# NixieDriver.net
KiCad netlist of a schematic drawn in EAGLE
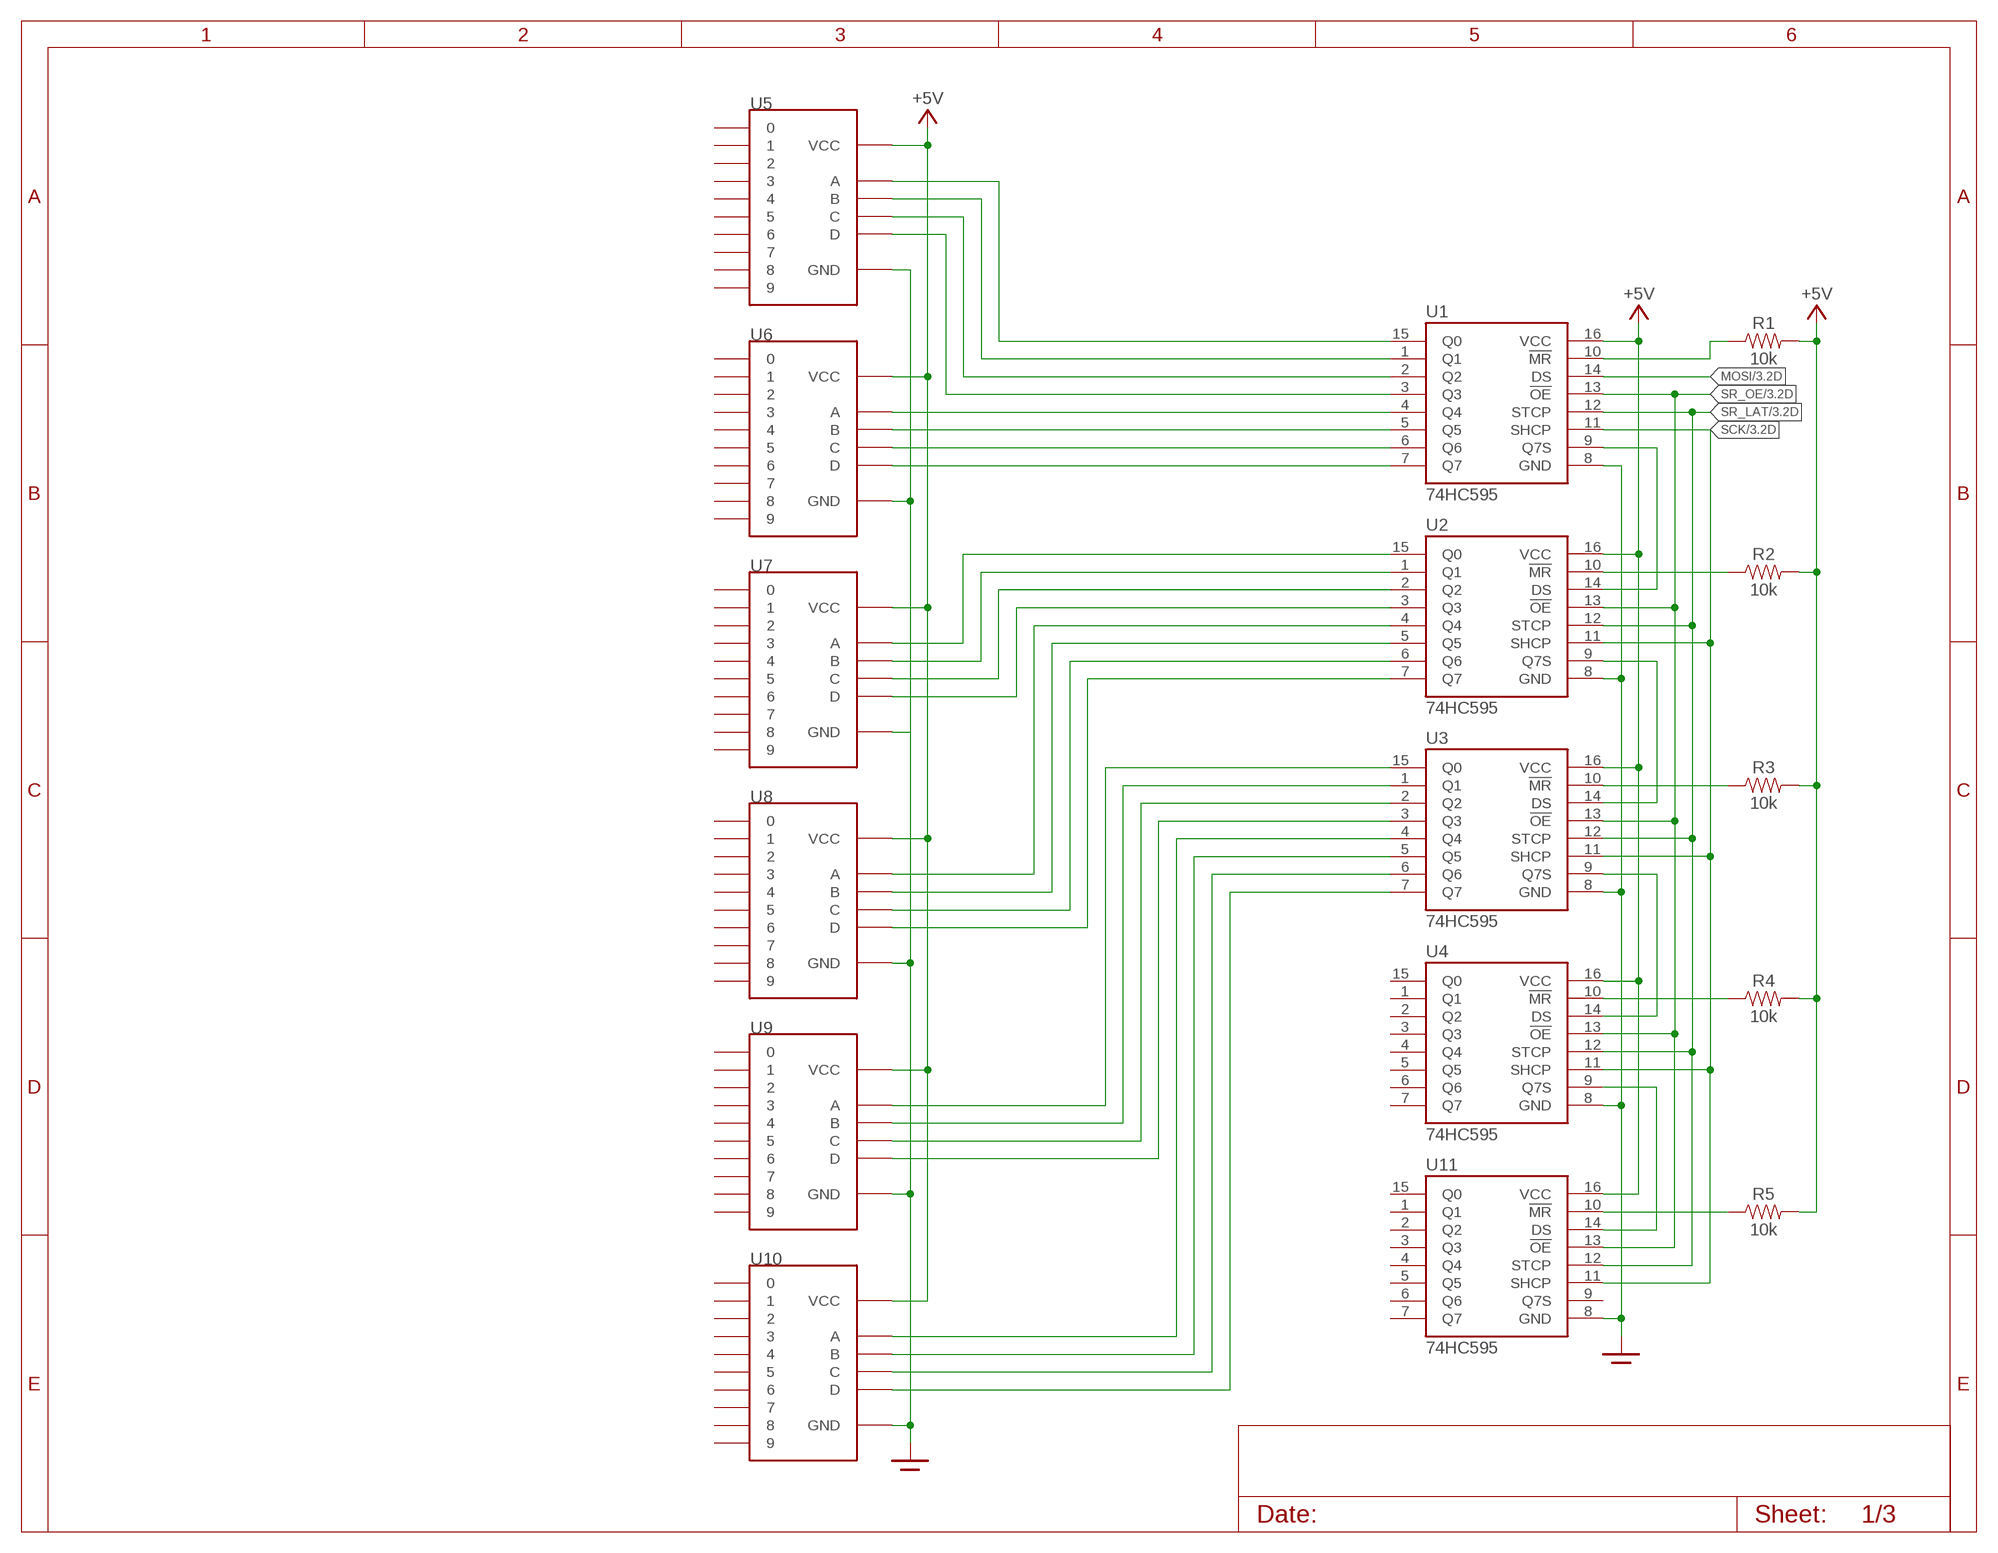
[diagram p0: schematic, sheet 1]
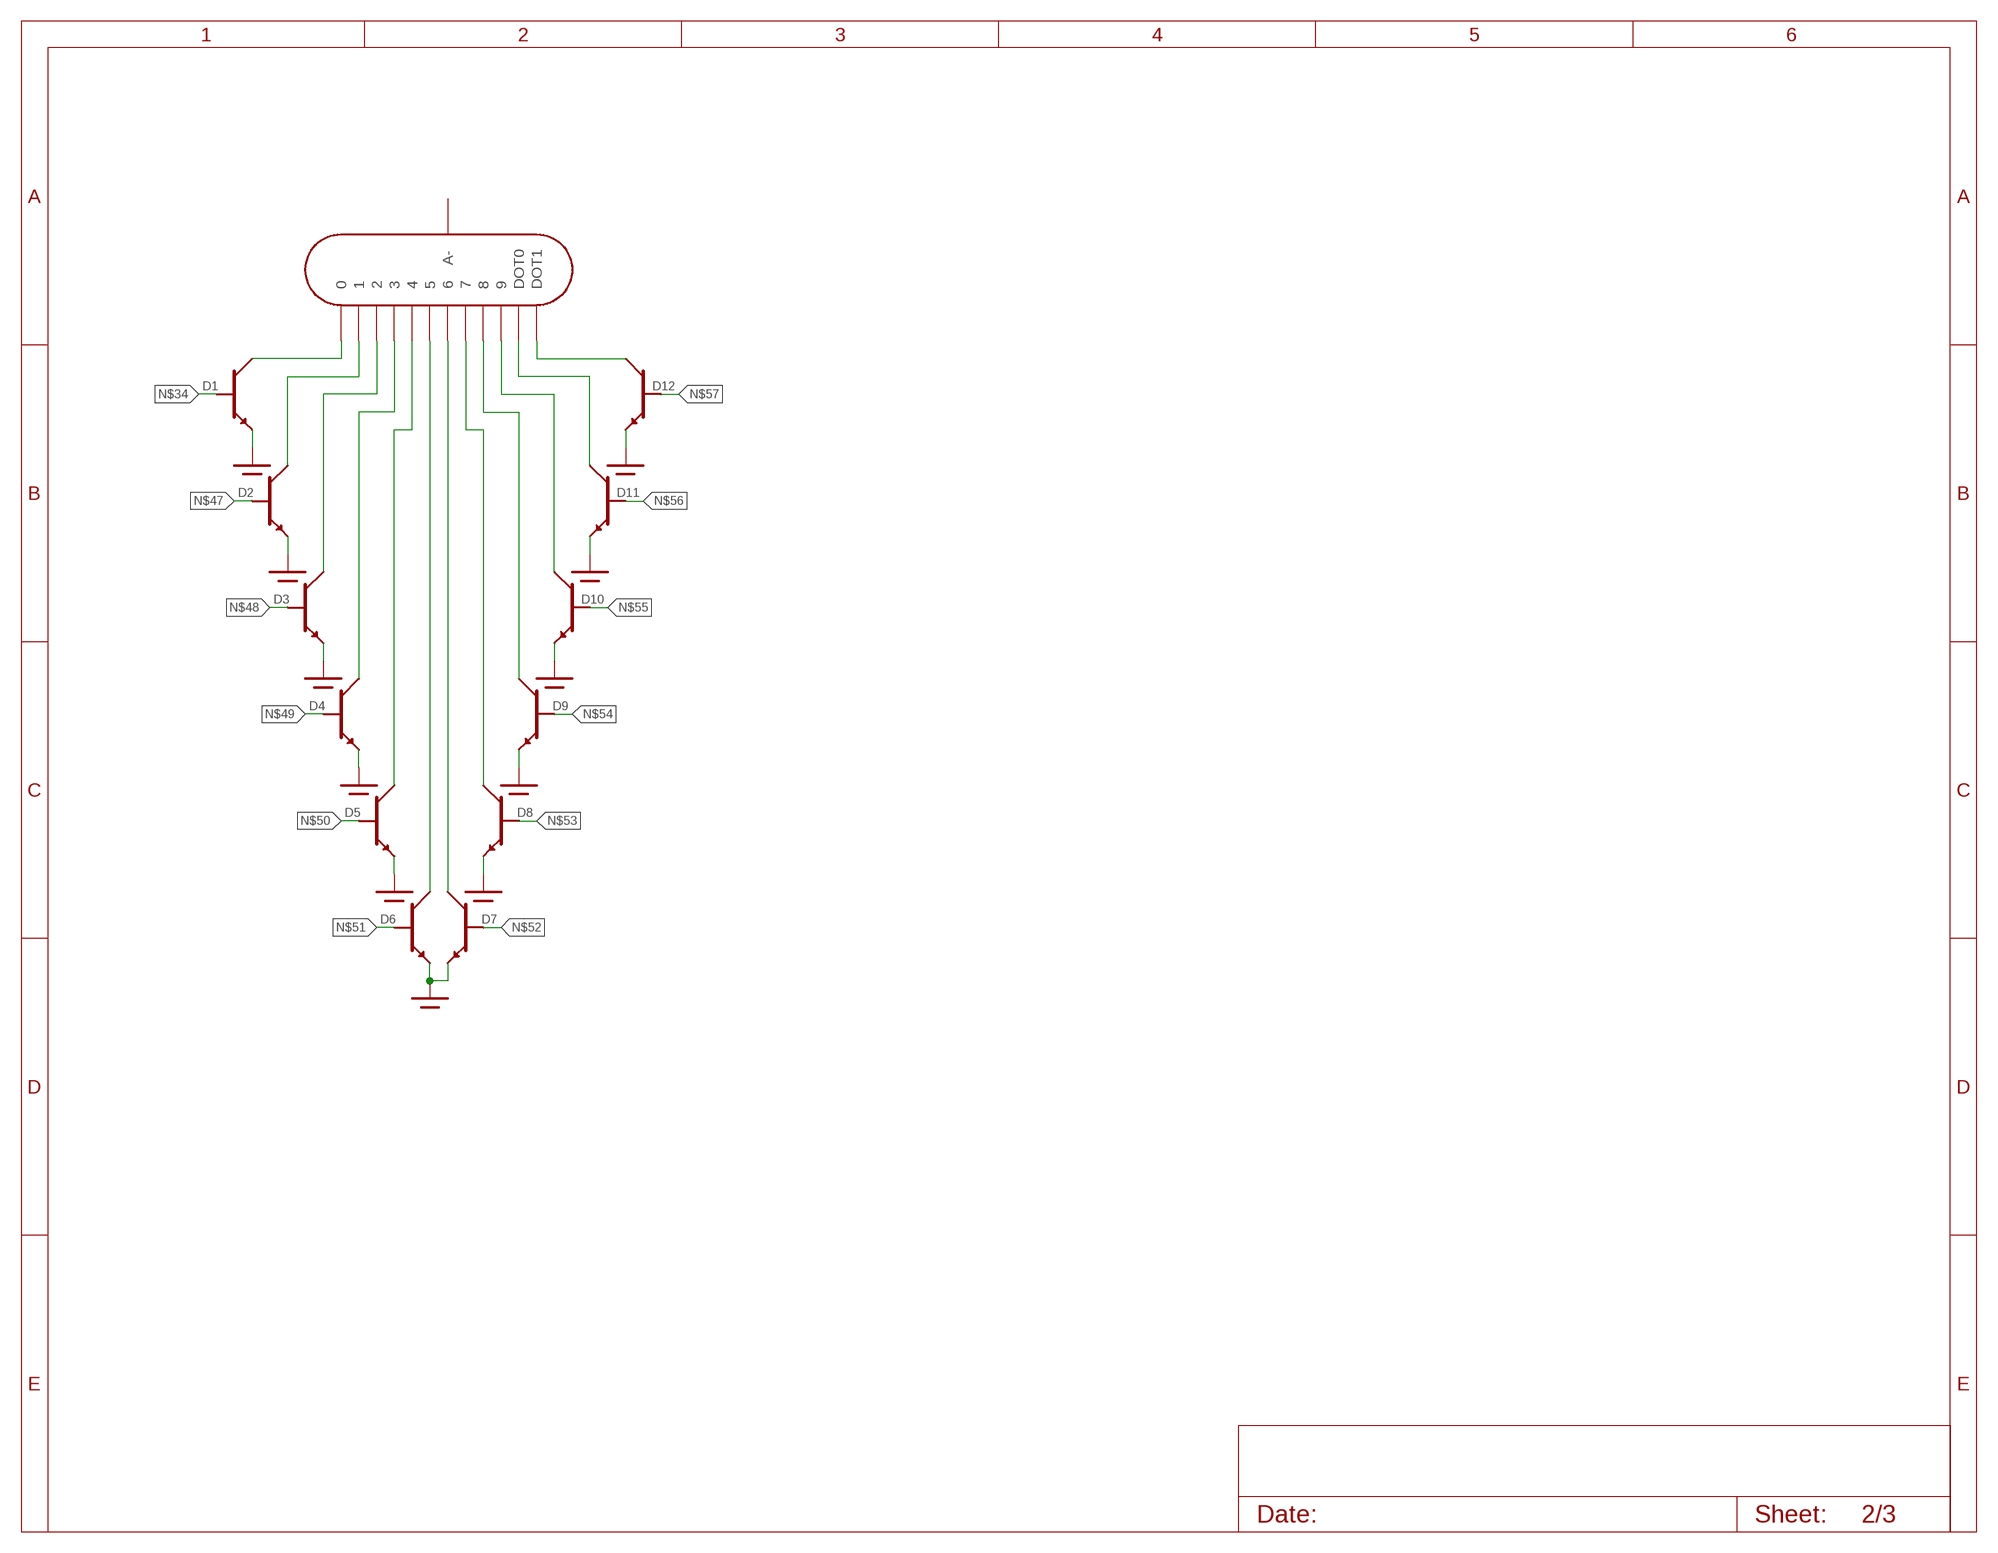
[diagram p1: schematic, sheet 2]
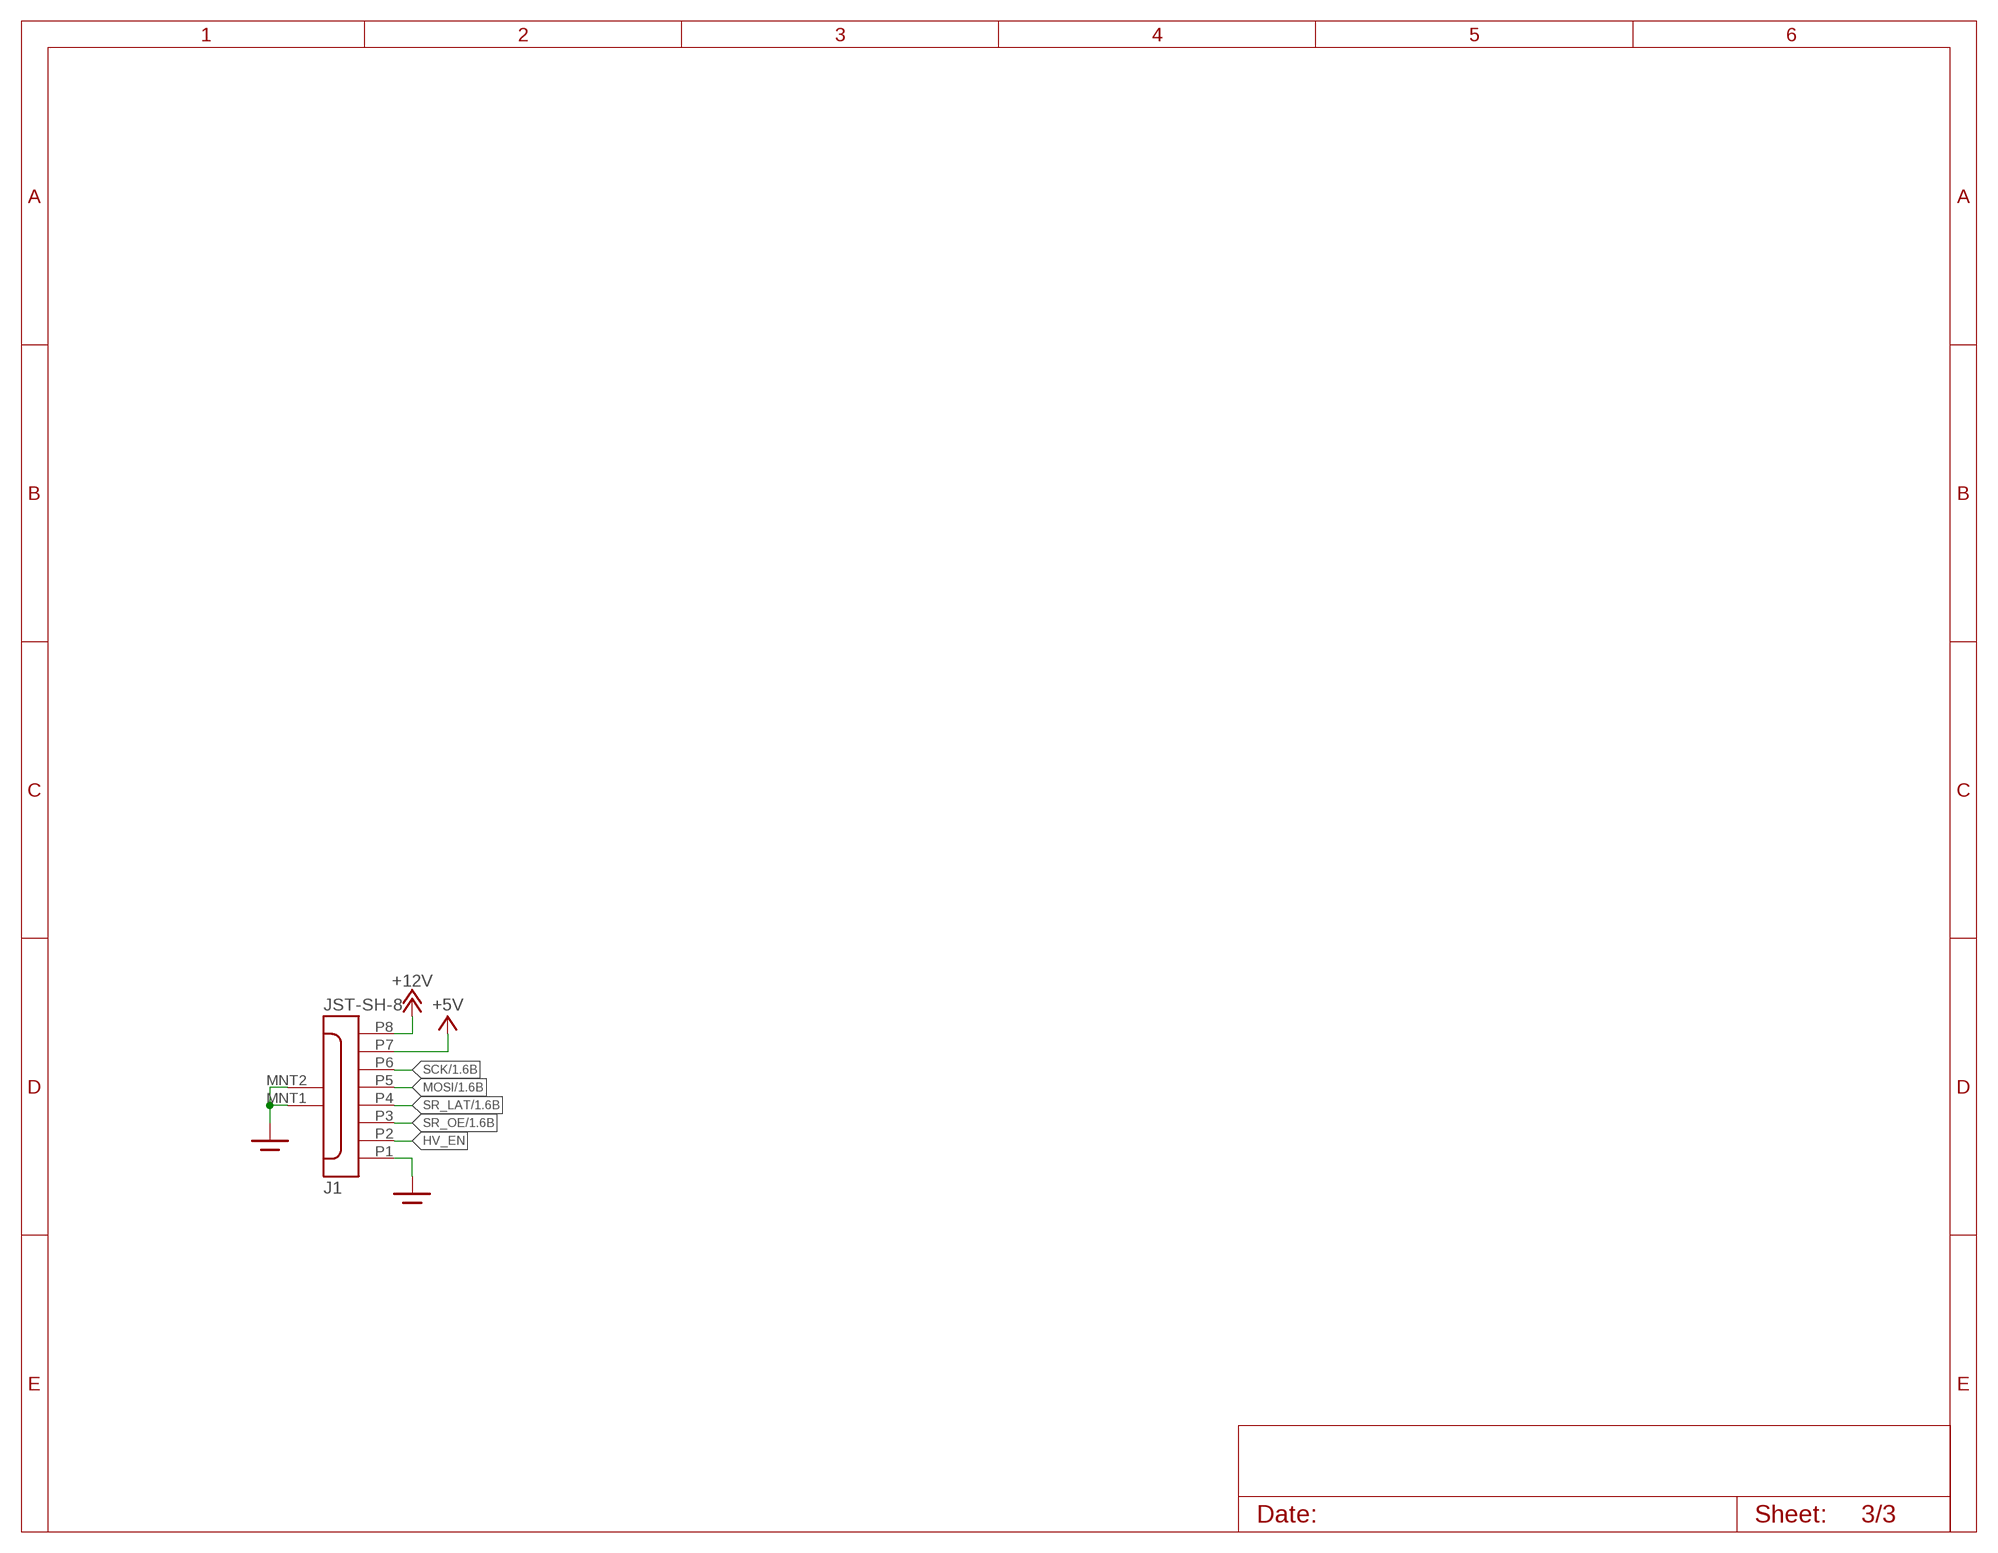
[diagram p2: schematic, sheet 3]

(export (version "E")
  (design (tool "Eeschema 10.0.6"))
  (components
    (comp (ref "R1")
      (value "10k")
      (footprint "eagle-import:SMD-805")
      (libsource (lib "eagle-import") (part "RESISTOR0805"))
    )
    (comp (ref "R2")
      (value "10k")
      (footprint "eagle-import:SMD-805")
      (libsource (lib "eagle-import") (part "RESISTOR0805"))
    )
    (comp (ref "R3")
      (value "10k")
      (footprint "eagle-import:SMD-805")
      (libsource (lib "eagle-import") (part "RESISTOR0805"))
    )
    (comp (ref "R4")
      (value "10k")
      (footprint "eagle-import:SMD-805")
      (libsource (lib "eagle-import") (part "RESISTOR0805"))
    )
    (comp (ref "R5")
      (value "10k")
      (footprint "eagle-import:SMD-805")
      (libsource (lib "eagle-import") (part "RESISTOR0805"))
    )
    (comp (ref "U1")
      (value "74HC595")
      (footprint "eagle-import:TSSOP-16")
      (libsource (lib "eagle-import") (part "74HC595"))
    )
    (comp (ref "U2")
      (value "74HC595")
      (footprint "eagle-import:TSSOP-16")
      (libsource (lib "eagle-import") (part "74HC595"))
    )
    (comp (ref "U3")
      (value "74HC595")
      (footprint "eagle-import:TSSOP-16")
      (libsource (lib "eagle-import") (part "74HC595"))
    )
    (comp (ref "U4")
      (value "74HC595")
      (footprint "eagle-import:TSSOP-16")
      (libsource (lib "eagle-import") (part "74HC595"))
    )
    (comp (ref "U5")
      (value "74HC42")
      (footprint "eagle-import:SOIC-16")
      (libsource (lib "eagle-import") (part "74HC42"))
    )
    (comp (ref "U6")
      (value "74HC42")
      (footprint "eagle-import:SOIC-16")
      (libsource (lib "eagle-import") (part "74HC42"))
    )
    (comp (ref "U7")
      (value "74HC42")
      (footprint "eagle-import:SOIC-16")
      (libsource (lib "eagle-import") (part "74HC42"))
    )
    (comp (ref "U8")
      (value "74HC42")
      (footprint "eagle-import:SOIC-16")
      (libsource (lib "eagle-import") (part "74HC42"))
    )
    (comp (ref "U9")
      (value "74HC42")
      (footprint "eagle-import:SOIC-16")
      (libsource (lib "eagle-import") (part "74HC42"))
    )
    (comp (ref "U10")
      (value "74HC42")
      (footprint "eagle-import:SOIC-16")
      (libsource (lib "eagle-import") (part "74HC42"))
    )
    (comp (ref "U11")
      (value "74HC595")
      (footprint "eagle-import:TSSOP-16")
      (libsource (lib "eagle-import") (part "74HC595"))
    )
    (comp (ref "D1")
      (value "BJT-NPN")
      (footprint "eagle-import:SOT-23-3")
      (libsource (lib "eagle-import") (part "BJT-NPN"))
    )
    (comp (ref "D2")
      (value "BJT-NPN")
      (footprint "eagle-import:SOT-23-3")
      (libsource (lib "eagle-import") (part "BJT-NPN"))
    )
    (comp (ref "D3")
      (value "BJT-NPN")
      (footprint "eagle-import:SOT-23-3")
      (libsource (lib "eagle-import") (part "BJT-NPN"))
    )
    (comp (ref "D4")
      (value "BJT-NPN")
      (footprint "eagle-import:SOT-23-3")
      (libsource (lib "eagle-import") (part "BJT-NPN"))
    )
    (comp (ref "D5")
      (value "BJT-NPN")
      (footprint "eagle-import:SOT-23-3")
      (libsource (lib "eagle-import") (part "BJT-NPN"))
    )
    (comp (ref "D6")
      (value "BJT-NPN")
      (footprint "eagle-import:SOT-23-3")
      (libsource (lib "eagle-import") (part "BJT-NPN"))
    )
    (comp (ref "D7")
      (value "BJT-NPN")
      (footprint "eagle-import:SOT-23-3")
      (libsource (lib "eagle-import") (part "BJT-NPN"))
    )
    (comp (ref "D8")
      (value "BJT-NPN")
      (footprint "eagle-import:SOT-23-3")
      (libsource (lib "eagle-import") (part "BJT-NPN"))
    )
    (comp (ref "D9")
      (value "BJT-NPN")
      (footprint "eagle-import:SOT-23-3")
      (libsource (lib "eagle-import") (part "BJT-NPN"))
    )
    (comp (ref "D10")
      (value "BJT-NPN")
      (footprint "eagle-import:SOT-23-3")
      (libsource (lib "eagle-import") (part "BJT-NPN"))
    )
    (comp (ref "D11")
      (value "BJT-NPN")
      (footprint "eagle-import:SOT-23-3")
      (libsource (lib "eagle-import") (part "BJT-NPN"))
    )
    (comp (ref "D12")
      (value "BJT-NPN")
      (footprint "eagle-import:SOT-23-3")
      (libsource (lib "eagle-import") (part "BJT-NPN"))
    )
    (comp (ref "N1")
      (value "IN-16-NIXIE")
      (footprint "eagle-import:IN-16-NIXIE")
      (libsource (lib "eagle-import") (part "IN-16-NIXIE"))
    )
    (comp (ref "J1")
      (value "JST-SH-8")
      (footprint "eagle-import:JST-SH-8")
      (libsource (lib "eagle-import") (part "JST-SH-8"))
    )
  )
  (nets
    (net (code "1") (name "+5V") (class "Default")
      (node (ref "J1") (pin "P7") (pinfunction "7_P7") (pintype "passive"))
      (node (ref "R1") (pin "2") (pinfunction "2_2") (pintype "passive"))
      (node (ref "R2") (pin "2") (pinfunction "2_2") (pintype "passive"))
      (node (ref "R3") (pin "2") (pinfunction "2_2") (pintype "passive"))
      (node (ref "R4") (pin "2") (pinfunction "2_2") (pintype "passive"))
      (node (ref "R5") (pin "2") (pinfunction "2_2") (pintype "passive"))
      (node (ref "U1") (pin "16") (pinfunction "VCC_16") (pintype "bidirectional"))
      (node (ref "U10") (pin "16") (pinfunction "VCC_16") (pintype "bidirectional"))
      (node (ref "U11") (pin "16") (pinfunction "VCC_16") (pintype "bidirectional"))
      (node (ref "U2") (pin "16") (pinfunction "VCC_16") (pintype "bidirectional"))
      (node (ref "U3") (pin "16") (pinfunction "VCC_16") (pintype "bidirectional"))
      (node (ref "U4") (pin "16") (pinfunction "VCC_16") (pintype "bidirectional"))
      (node (ref "U5") (pin "16") (pinfunction "VCC_16") (pintype "bidirectional"))
      (node (ref "U6") (pin "16") (pinfunction "VCC_16") (pintype "bidirectional"))
      (node (ref "U7") (pin "16") (pinfunction "VCC_16") (pintype "bidirectional"))
      (node (ref "U8") (pin "16") (pinfunction "VCC_16") (pintype "bidirectional"))
      (node (ref "U9") (pin "16") (pinfunction "VCC_16") (pintype "bidirectional"))
    )
    (net (code "2") (name "+12V") (class "Default")
      (node (ref "J1") (pin "P8") (pinfunction "8_P8") (pintype "passive"))
    )
    (net (code "3") (name "GND") (class "Default")
      (node (ref "D1") (pin "2") (pinfunction "P$2_2") (pintype "bidirectional"))
      (node (ref "D10") (pin "2") (pinfunction "P$2_2") (pintype "bidirectional"))
      (node (ref "D11") (pin "2") (pinfunction "P$2_2") (pintype "bidirectional"))
      (node (ref "D12") (pin "2") (pinfunction "P$2_2") (pintype "bidirectional"))
      (node (ref "D2") (pin "2") (pinfunction "P$2_2") (pintype "bidirectional"))
      (node (ref "D3") (pin "2") (pinfunction "P$2_2") (pintype "bidirectional"))
      (node (ref "D4") (pin "2") (pinfunction "P$2_2") (pintype "bidirectional"))
      (node (ref "D5") (pin "2") (pinfunction "P$2_2") (pintype "bidirectional"))
      (node (ref "D6") (pin "2") (pinfunction "P$2_2") (pintype "bidirectional"))
      (node (ref "D7") (pin "2") (pinfunction "P$2_2") (pintype "bidirectional"))
      (node (ref "D8") (pin "2") (pinfunction "P$2_2") (pintype "bidirectional"))
      (node (ref "D9") (pin "2") (pinfunction "P$2_2") (pintype "bidirectional"))
      (node (ref "J1") (pin "MNT1") (pinfunction "MNT1_MNT1") (pintype "power_in"))
      (node (ref "J1") (pin "MNT2") (pinfunction "MNT2_MNT2") (pintype "power_in"))
      (node (ref "J1") (pin "P1") (pinfunction "1_P1") (pintype "passive"))
      (node (ref "U1") (pin "8") (pinfunction "GND_8") (pintype "bidirectional"))
      (node (ref "U10") (pin "8") (pinfunction "GND_8") (pintype "bidirectional"))
      (node (ref "U11") (pin "8") (pinfunction "GND_8") (pintype "bidirectional"))
      (node (ref "U2") (pin "8") (pinfunction "GND_8") (pintype "bidirectional"))
      (node (ref "U3") (pin "8") (pinfunction "GND_8") (pintype "bidirectional"))
      (node (ref "U4") (pin "8") (pinfunction "GND_8") (pintype "bidirectional"))
      (node (ref "U5") (pin "8") (pinfunction "GND_8") (pintype "bidirectional"))
      (node (ref "U6") (pin "8") (pinfunction "GND_8") (pintype "bidirectional"))
      (node (ref "U7") (pin "8") (pinfunction "GND_8") (pintype "bidirectional"))
      (node (ref "U8") (pin "8") (pinfunction "GND_8") (pintype "bidirectional"))
      (node (ref "U9") (pin "8") (pinfunction "GND_8") (pintype "bidirectional"))
    )
    (net (code "4") (name "HV_EN") (class "Default")
      (node (ref "J1") (pin "P2") (pinfunction "2_P2") (pintype "passive"))
    )
    (net (code "5") (name "MOSI") (class "Default")
      (node (ref "J1") (pin "P5") (pinfunction "5_P5") (pintype "passive"))
      (node (ref "U1") (pin "14") (pinfunction "DS_14") (pintype "bidirectional"))
    )
    (net (code "6") (name "N$34") (class "Default")
      (node (ref "D1") (pin "3") (pinfunction "P$3_3") (pintype "bidirectional"))
    )
    (net (code "7") (name "N$47") (class "Default")
      (node (ref "D2") (pin "3") (pinfunction "P$3_3") (pintype "bidirectional"))
    )
    (net (code "8") (name "N$48") (class "Default")
      (node (ref "D3") (pin "3") (pinfunction "P$3_3") (pintype "bidirectional"))
    )
    (net (code "9") (name "N$49") (class "Default")
      (node (ref "D4") (pin "3") (pinfunction "P$3_3") (pintype "bidirectional"))
    )
    (net (code "10") (name "N$50") (class "Default")
      (node (ref "D5") (pin "3") (pinfunction "P$3_3") (pintype "bidirectional"))
    )
    (net (code "11") (name "N$51") (class "Default")
      (node (ref "D6") (pin "3") (pinfunction "P$3_3") (pintype "bidirectional"))
    )
    (net (code "12") (name "N$52") (class "Default")
      (node (ref "D7") (pin "3") (pinfunction "P$3_3") (pintype "bidirectional"))
    )
    (net (code "13") (name "N$53") (class "Default")
      (node (ref "D8") (pin "3") (pinfunction "P$3_3") (pintype "bidirectional"))
    )
    (net (code "14") (name "N$54") (class "Default")
      (node (ref "D9") (pin "3") (pinfunction "P$3_3") (pintype "bidirectional"))
    )
    (net (code "15") (name "N$55") (class "Default")
      (node (ref "D10") (pin "3") (pinfunction "P$3_3") (pintype "bidirectional"))
    )
    (net (code "16") (name "N$56") (class "Default")
      (node (ref "D11") (pin "3") (pinfunction "P$3_3") (pintype "bidirectional"))
    )
    (net (code "17") (name "N$57") (class "Default")
      (node (ref "D12") (pin "3") (pinfunction "P$3_3") (pintype "bidirectional"))
    )
    (net (code "18") (name "Net-(D1-P$1)") (class "Default")
      (node (ref "D1") (pin "1") (pinfunction "P$1_1") (pintype "bidirectional"))
      (node (ref "N1") (pin "1") (pinfunction "0_1") (pintype "bidirectional"))
    )
    (net (code "19") (name "Net-(D2-P$1)") (class "Default")
      (node (ref "D2") (pin "1") (pinfunction "P$1_1") (pintype "bidirectional"))
      (node (ref "N1") (pin "2") (pinfunction "1_2") (pintype "bidirectional"))
    )
    (net (code "20") (name "Net-(D3-P$1)") (class "Default")
      (node (ref "D3") (pin "1") (pinfunction "P$1_1") (pintype "bidirectional"))
      (node (ref "N1") (pin "3") (pinfunction "2_3") (pintype "bidirectional"))
    )
    (net (code "21") (name "Net-(D4-P$1)") (class "Default")
      (node (ref "D4") (pin "1") (pinfunction "P$1_1") (pintype "bidirectional"))
      (node (ref "N1") (pin "4") (pinfunction "3_4") (pintype "bidirectional"))
    )
    (net (code "22") (name "Net-(D5-P$1)") (class "Default")
      (node (ref "D5") (pin "1") (pinfunction "P$1_1") (pintype "bidirectional"))
      (node (ref "N1") (pin "5") (pinfunction "4_5") (pintype "bidirectional"))
    )
    (net (code "23") (name "Net-(D6-P$1)") (class "Default")
      (node (ref "D6") (pin "1") (pinfunction "P$1_1") (pintype "bidirectional"))
      (node (ref "N1") (pin "6") (pinfunction "5_6") (pintype "bidirectional"))
    )
    (net (code "24") (name "Net-(D7-P$1)") (class "Default")
      (node (ref "D7") (pin "1") (pinfunction "P$1_1") (pintype "bidirectional"))
      (node (ref "N1") (pin "7") (pinfunction "6_7") (pintype "bidirectional"))
    )
    (net (code "25") (name "Net-(D8-P$1)") (class "Default")
      (node (ref "D8") (pin "1") (pinfunction "P$1_1") (pintype "bidirectional"))
      (node (ref "N1") (pin "8") (pinfunction "7_8") (pintype "bidirectional"))
    )
    (net (code "26") (name "Net-(D9-P$1)") (class "Default")
      (node (ref "D9") (pin "1") (pinfunction "P$1_1") (pintype "bidirectional"))
      (node (ref "N1") (pin "9") (pinfunction "8_9") (pintype "bidirectional"))
    )
    (net (code "27") (name "Net-(D10-P$1)") (class "Default")
      (node (ref "D10") (pin "1") (pinfunction "P$1_1") (pintype "bidirectional"))
      (node (ref "N1") (pin "10") (pinfunction "9_10") (pintype "bidirectional"))
    )
    (net (code "28") (name "Net-(D11-P$1)") (class "Default")
      (node (ref "D11") (pin "1") (pinfunction "P$1_1") (pintype "bidirectional"))
      (node (ref "N1") (pin "12") (pinfunction "DOT0_12") (pintype "bidirectional"))
    )
    (net (code "29") (name "Net-(D12-P$1)") (class "Default")
      (node (ref "D12") (pin "1") (pinfunction "P$1_1") (pintype "bidirectional"))
      (node (ref "N1") (pin "13") (pinfunction "DOT1_13") (pintype "bidirectional"))
    )
    (net (code "30") (name "Net-(U1-Q0)") (class "Default")
      (node (ref "U1") (pin "15") (pinfunction "Q0_15") (pintype "bidirectional"))
      (node (ref "U5") (pin "15") (pinfunction "A_15") (pintype "bidirectional"))
    )
    (net (code "31") (name "Net-(U1-Q1)") (class "Default")
      (node (ref "U1") (pin "1") (pinfunction "Q1_1") (pintype "bidirectional"))
      (node (ref "U5") (pin "14") (pinfunction "B_14") (pintype "bidirectional"))
    )
    (net (code "32") (name "Net-(U1-Q2)") (class "Default")
      (node (ref "U1") (pin "2") (pinfunction "Q2_2") (pintype "bidirectional"))
      (node (ref "U5") (pin "13") (pinfunction "C_13") (pintype "bidirectional"))
    )
    (net (code "33") (name "Net-(U1-Q3)") (class "Default")
      (node (ref "U1") (pin "3") (pinfunction "Q3_3") (pintype "bidirectional"))
      (node (ref "U5") (pin "12") (pinfunction "D_12") (pintype "bidirectional"))
    )
    (net (code "34") (name "Net-(U1-Q4)") (class "Default")
      (node (ref "U1") (pin "4") (pinfunction "Q4_4") (pintype "bidirectional"))
      (node (ref "U6") (pin "15") (pinfunction "A_15") (pintype "bidirectional"))
    )
    (net (code "35") (name "Net-(U1-Q5)") (class "Default")
      (node (ref "U1") (pin "5") (pinfunction "Q5_5") (pintype "bidirectional"))
      (node (ref "U6") (pin "14") (pinfunction "B_14") (pintype "bidirectional"))
    )
    (net (code "36") (name "Net-(U1-Q6)") (class "Default")
      (node (ref "U1") (pin "6") (pinfunction "Q6_6") (pintype "bidirectional"))
      (node (ref "U6") (pin "13") (pinfunction "C_13") (pintype "bidirectional"))
    )
    (net (code "37") (name "Net-(U1-Q7)") (class "Default")
      (node (ref "U1") (pin "7") (pinfunction "Q7_7") (pintype "bidirectional"))
      (node (ref "U6") (pin "12") (pinfunction "D_12") (pintype "bidirectional"))
    )
    (net (code "38") (name "Net-(U1-Q7S)") (class "Default")
      (node (ref "U1") (pin "9") (pinfunction "Q7S_9") (pintype "bidirectional"))
      (node (ref "U2") (pin "14") (pinfunction "DS_14") (pintype "bidirectional"))
    )
    (net (code "39") (name "Net-(U1-~{MR})") (class "Default")
      (node (ref "R1") (pin "1") (pinfunction "1_1") (pintype "passive"))
      (node (ref "U1") (pin "10") (pinfunction "~{MR}_10") (pintype "bidirectional"))
    )
    (net (code "40") (name "Net-(U2-Q0)") (class "Default")
      (node (ref "U2") (pin "15") (pinfunction "Q0_15") (pintype "bidirectional"))
      (node (ref "U7") (pin "15") (pinfunction "A_15") (pintype "bidirectional"))
    )
    (net (code "41") (name "Net-(U2-Q1)") (class "Default")
      (node (ref "U2") (pin "1") (pinfunction "Q1_1") (pintype "bidirectional"))
      (node (ref "U7") (pin "14") (pinfunction "B_14") (pintype "bidirectional"))
    )
    (net (code "42") (name "Net-(U2-Q2)") (class "Default")
      (node (ref "U2") (pin "2") (pinfunction "Q2_2") (pintype "bidirectional"))
      (node (ref "U7") (pin "13") (pinfunction "C_13") (pintype "bidirectional"))
    )
    (net (code "43") (name "Net-(U2-Q3)") (class "Default")
      (node (ref "U2") (pin "3") (pinfunction "Q3_3") (pintype "bidirectional"))
      (node (ref "U7") (pin "12") (pinfunction "D_12") (pintype "bidirectional"))
    )
    (net (code "44") (name "Net-(U2-Q4)") (class "Default")
      (node (ref "U2") (pin "4") (pinfunction "Q4_4") (pintype "bidirectional"))
      (node (ref "U8") (pin "15") (pinfunction "A_15") (pintype "bidirectional"))
    )
    (net (code "45") (name "Net-(U2-Q5)") (class "Default")
      (node (ref "U2") (pin "5") (pinfunction "Q5_5") (pintype "bidirectional"))
      (node (ref "U8") (pin "14") (pinfunction "B_14") (pintype "bidirectional"))
    )
    (net (code "46") (name "Net-(U2-Q6)") (class "Default")
      (node (ref "U2") (pin "6") (pinfunction "Q6_6") (pintype "bidirectional"))
      (node (ref "U8") (pin "13") (pinfunction "C_13") (pintype "bidirectional"))
    )
    (net (code "47") (name "Net-(U2-Q7)") (class "Default")
      (node (ref "U2") (pin "7") (pinfunction "Q7_7") (pintype "bidirectional"))
      (node (ref "U8") (pin "12") (pinfunction "D_12") (pintype "bidirectional"))
    )
    (net (code "48") (name "Net-(U2-Q7S)") (class "Default")
      (node (ref "U2") (pin "9") (pinfunction "Q7S_9") (pintype "bidirectional"))
      (node (ref "U3") (pin "14") (pinfunction "DS_14") (pintype "bidirectional"))
    )
    (net (code "49") (name "Net-(U2-~{MR})") (class "Default")
      (node (ref "R2") (pin "1") (pinfunction "1_1") (pintype "passive"))
      (node (ref "U2") (pin "10") (pinfunction "~{MR}_10") (pintype "bidirectional"))
    )
    (net (code "50") (name "Net-(U3-Q0)") (class "Default")
      (node (ref "U3") (pin "15") (pinfunction "Q0_15") (pintype "bidirectional"))
      (node (ref "U9") (pin "15") (pinfunction "A_15") (pintype "bidirectional"))
    )
    (net (code "51") (name "Net-(U3-Q1)") (class "Default")
      (node (ref "U3") (pin "1") (pinfunction "Q1_1") (pintype "bidirectional"))
      (node (ref "U9") (pin "14") (pinfunction "B_14") (pintype "bidirectional"))
    )
    (net (code "52") (name "Net-(U3-Q2)") (class "Default")
      (node (ref "U3") (pin "2") (pinfunction "Q2_2") (pintype "bidirectional"))
      (node (ref "U9") (pin "13") (pinfunction "C_13") (pintype "bidirectional"))
    )
    (net (code "53") (name "Net-(U3-Q3)") (class "Default")
      (node (ref "U3") (pin "3") (pinfunction "Q3_3") (pintype "bidirectional"))
      (node (ref "U9") (pin "12") (pinfunction "D_12") (pintype "bidirectional"))
    )
    (net (code "54") (name "Net-(U3-Q7S)") (class "Default")
      (node (ref "U3") (pin "9") (pinfunction "Q7S_9") (pintype "bidirectional"))
      (node (ref "U4") (pin "14") (pinfunction "DS_14") (pintype "bidirectional"))
    )
    (net (code "55") (name "Net-(U3-~{MR})") (class "Default")
      (node (ref "R3") (pin "1") (pinfunction "1_1") (pintype "passive"))
      (node (ref "U3") (pin "10") (pinfunction "~{MR}_10") (pintype "bidirectional"))
    )
    (net (code "56") (name "Net-(U4-~{MR})") (class "Default")
      (node (ref "R4") (pin "1") (pinfunction "1_1") (pintype "passive"))
      (node (ref "U4") (pin "10") (pinfunction "~{MR}_10") (pintype "bidirectional"))
    )
    (net (code "57") (name "Net-(U10-A)") (class "Default")
      (node (ref "U10") (pin "15") (pinfunction "A_15") (pintype "bidirectional"))
      (node (ref "U3") (pin "4") (pinfunction "Q4_4") (pintype "bidirectional"))
    )
    (net (code "58") (name "Net-(U10-B)") (class "Default")
      (node (ref "U10") (pin "14") (pinfunction "B_14") (pintype "bidirectional"))
      (node (ref "U3") (pin "5") (pinfunction "Q5_5") (pintype "bidirectional"))
    )
    (net (code "59") (name "Net-(U10-C)") (class "Default")
      (node (ref "U10") (pin "13") (pinfunction "C_13") (pintype "bidirectional"))
      (node (ref "U3") (pin "6") (pinfunction "Q6_6") (pintype "bidirectional"))
    )
    (net (code "60") (name "Net-(U10-D)") (class "Default")
      (node (ref "U10") (pin "12") (pinfunction "D_12") (pintype "bidirectional"))
      (node (ref "U3") (pin "7") (pinfunction "Q7_7") (pintype "bidirectional"))
    )
    (net (code "61") (name "Net-(U11-DS)") (class "Default")
      (node (ref "U11") (pin "14") (pinfunction "DS_14") (pintype "bidirectional"))
      (node (ref "U4") (pin "9") (pinfunction "Q7S_9") (pintype "bidirectional"))
    )
    (net (code "62") (name "Net-(U11-~{MR})") (class "Default")
      (node (ref "R5") (pin "1") (pinfunction "1_1") (pintype "passive"))
      (node (ref "U11") (pin "10") (pinfunction "~{MR}_10") (pintype "bidirectional"))
    )
    (net (code "63") (name "SCK") (class "Default")
      (node (ref "J1") (pin "P6") (pinfunction "6_P6") (pintype "passive"))
      (node (ref "U1") (pin "11") (pinfunction "SHCP_11") (pintype "bidirectional"))
      (node (ref "U11") (pin "11") (pinfunction "SHCP_11") (pintype "bidirectional"))
      (node (ref "U2") (pin "11") (pinfunction "SHCP_11") (pintype "bidirectional"))
      (node (ref "U3") (pin "11") (pinfunction "SHCP_11") (pintype "bidirectional"))
      (node (ref "U4") (pin "11") (pinfunction "SHCP_11") (pintype "bidirectional"))
    )
    (net (code "64") (name "SR_LAT") (class "Default")
      (node (ref "J1") (pin "P4") (pinfunction "4_P4") (pintype "passive"))
      (node (ref "U1") (pin "12") (pinfunction "STCP_12") (pintype "bidirectional"))
      (node (ref "U11") (pin "12") (pinfunction "STCP_12") (pintype "bidirectional"))
      (node (ref "U2") (pin "12") (pinfunction "STCP_12") (pintype "bidirectional"))
      (node (ref "U3") (pin "12") (pinfunction "STCP_12") (pintype "bidirectional"))
      (node (ref "U4") (pin "12") (pinfunction "STCP_12") (pintype "bidirectional"))
    )
    (net (code "65") (name "SR_OE") (class "Default")
      (node (ref "J1") (pin "P3") (pinfunction "3_P3") (pintype "passive"))
      (node (ref "U1") (pin "13") (pinfunction "~{OE}_13") (pintype "bidirectional"))
      (node (ref "U11") (pin "13") (pinfunction "~{OE}_13") (pintype "bidirectional"))
      (node (ref "U2") (pin "13") (pinfunction "~{OE}_13") (pintype "bidirectional"))
      (node (ref "U3") (pin "13") (pinfunction "~{OE}_13") (pintype "bidirectional"))
      (node (ref "U4") (pin "13") (pinfunction "~{OE}_13") (pintype "bidirectional"))
    )
    (net (code "66") (name "unconnected-(N1-A--Pad11)") (class "Default")
      (node (ref "N1") (pin "11") (pinfunction "A-_11") (pintype "bidirectional"))
    )
    (net (code "67") (name "unconnected-(U4-Q0-Pad15)") (class "Default")
      (node (ref "U4") (pin "15") (pinfunction "Q0_15") (pintype "bidirectional"))
    )
    (net (code "68") (name "unconnected-(U4-Q1-Pad1)") (class "Default")
      (node (ref "U4") (pin "1") (pinfunction "Q1_1") (pintype "bidirectional"))
    )
    (net (code "69") (name "unconnected-(U4-Q2-Pad2)") (class "Default")
      (node (ref "U4") (pin "2") (pinfunction "Q2_2") (pintype "bidirectional"))
    )
    (net (code "70") (name "unconnected-(U4-Q3-Pad3)") (class "Default")
      (node (ref "U4") (pin "3") (pinfunction "Q3_3") (pintype "bidirectional"))
    )
    (net (code "71") (name "unconnected-(U4-Q4-Pad4)") (class "Default")
      (node (ref "U4") (pin "4") (pinfunction "Q4_4") (pintype "bidirectional"))
    )
    (net (code "72") (name "unconnected-(U4-Q5-Pad5)") (class "Default")
      (node (ref "U4") (pin "5") (pinfunction "Q5_5") (pintype "bidirectional"))
    )
    (net (code "73") (name "unconnected-(U4-Q6-Pad6)") (class "Default")
      (node (ref "U4") (pin "6") (pinfunction "Q6_6") (pintype "bidirectional"))
    )
    (net (code "74") (name "unconnected-(U4-Q7-Pad7)") (class "Default")
      (node (ref "U4") (pin "7") (pinfunction "Q7_7") (pintype "bidirectional"))
    )
    (net (code "75") (name "unconnected-(U5-0-Pad1)") (class "Default")
      (node (ref "U5") (pin "1") (pinfunction "0_1") (pintype "bidirectional"))
    )
    (net (code "76") (name "unconnected-(U5-1-Pad2)") (class "Default")
      (node (ref "U5") (pin "2") (pinfunction "1_2") (pintype "bidirectional"))
    )
    (net (code "77") (name "unconnected-(U5-2-Pad3)") (class "Default")
      (node (ref "U5") (pin "3") (pinfunction "2_3") (pintype "bidirectional"))
    )
    (net (code "78") (name "unconnected-(U5-3-Pad4)") (class "Default")
      (node (ref "U5") (pin "4") (pinfunction "3_4") (pintype "bidirectional"))
    )
    (net (code "79") (name "unconnected-(U5-4-Pad5)") (class "Default")
      (node (ref "U5") (pin "5") (pinfunction "4_5") (pintype "bidirectional"))
    )
    (net (code "80") (name "unconnected-(U5-5-Pad6)") (class "Default")
      (node (ref "U5") (pin "6") (pinfunction "5_6") (pintype "bidirectional"))
    )
    (net (code "81") (name "unconnected-(U5-6-Pad7)") (class "Default")
      (node (ref "U5") (pin "7") (pinfunction "6_7") (pintype "bidirectional"))
    )
    (net (code "82") (name "unconnected-(U5-7-Pad9)") (class "Default")
      (node (ref "U5") (pin "9") (pinfunction "7_9") (pintype "bidirectional"))
    )
    (net (code "83") (name "unconnected-(U5-8-Pad10)") (class "Default")
      (node (ref "U5") (pin "10") (pinfunction "8_10") (pintype "bidirectional"))
    )
    (net (code "84") (name "unconnected-(U5-9-Pad11)") (class "Default")
      (node (ref "U5") (pin "11") (pinfunction "9_11") (pintype "bidirectional"))
    )
    (net (code "85") (name "unconnected-(U6-0-Pad1)") (class "Default")
      (node (ref "U6") (pin "1") (pinfunction "0_1") (pintype "bidirectional"))
    )
    (net (code "86") (name "unconnected-(U6-1-Pad2)") (class "Default")
      (node (ref "U6") (pin "2") (pinfunction "1_2") (pintype "bidirectional"))
    )
    (net (code "87") (name "unconnected-(U6-2-Pad3)") (class "Default")
      (node (ref "U6") (pin "3") (pinfunction "2_3") (pintype "bidirectional"))
    )
    (net (code "88") (name "unconnected-(U6-3-Pad4)") (class "Default")
      (node (ref "U6") (pin "4") (pinfunction "3_4") (pintype "bidirectional"))
    )
    (net (code "89") (name "unconnected-(U6-4-Pad5)") (class "Default")
      (node (ref "U6") (pin "5") (pinfunction "4_5") (pintype "bidirectional"))
    )
    (net (code "90") (name "unconnected-(U6-5-Pad6)") (class "Default")
      (node (ref "U6") (pin "6") (pinfunction "5_6") (pintype "bidirectional"))
    )
    (net (code "91") (name "unconnected-(U6-6-Pad7)") (class "Default")
      (node (ref "U6") (pin "7") (pinfunction "6_7") (pintype "bidirectional"))
    )
    (net (code "92") (name "unconnected-(U6-7-Pad9)") (class "Default")
      (node (ref "U6") (pin "9") (pinfunction "7_9") (pintype "bidirectional"))
    )
    (net (code "93") (name "unconnected-(U6-8-Pad10)") (class "Default")
      (node (ref "U6") (pin "10") (pinfunction "8_10") (pintype "bidirectional"))
    )
    (net (code "94") (name "unconnected-(U6-9-Pad11)") (class "Default")
      (node (ref "U6") (pin "11") (pinfunction "9_11") (pintype "bidirectional"))
    )
    (net (code "95") (name "unconnected-(U7-0-Pad1)") (class "Default")
      (node (ref "U7") (pin "1") (pinfunction "0_1") (pintype "bidirectional"))
    )
    (net (code "96") (name "unconnected-(U7-1-Pad2)") (class "Default")
      (node (ref "U7") (pin "2") (pinfunction "1_2") (pintype "bidirectional"))
    )
    (net (code "97") (name "unconnected-(U7-2-Pad3)") (class "Default")
      (node (ref "U7") (pin "3") (pinfunction "2_3") (pintype "bidirectional"))
    )
    (net (code "98") (name "unconnected-(U7-3-Pad4)") (class "Default")
      (node (ref "U7") (pin "4") (pinfunction "3_4") (pintype "bidirectional"))
    )
    (net (code "99") (name "unconnected-(U7-4-Pad5)") (class "Default")
      (node (ref "U7") (pin "5") (pinfunction "4_5") (pintype "bidirectional"))
    )
    (net (code "100") (name "unconnected-(U7-5-Pad6)") (class "Default")
      (node (ref "U7") (pin "6") (pinfunction "5_6") (pintype "bidirectional"))
    )
    (net (code "101") (name "unconnected-(U7-6-Pad7)") (class "Default")
      (node (ref "U7") (pin "7") (pinfunction "6_7") (pintype "bidirectional"))
    )
    (net (code "102") (name "unconnected-(U7-7-Pad9)") (class "Default")
      (node (ref "U7") (pin "9") (pinfunction "7_9") (pintype "bidirectional"))
    )
    (net (code "103") (name "unconnected-(U7-8-Pad10)") (class "Default")
      (node (ref "U7") (pin "10") (pinfunction "8_10") (pintype "bidirectional"))
    )
    (net (code "104") (name "unconnected-(U7-9-Pad11)") (class "Default")
      (node (ref "U7") (pin "11") (pinfunction "9_11") (pintype "bidirectional"))
    )
    (net (code "105") (name "unconnected-(U8-0-Pad1)") (class "Default")
      (node (ref "U8") (pin "1") (pinfunction "0_1") (pintype "bidirectional"))
    )
    (net (code "106") (name "unconnected-(U8-1-Pad2)") (class "Default")
      (node (ref "U8") (pin "2") (pinfunction "1_2") (pintype "bidirectional"))
    )
    (net (code "107") (name "unconnected-(U8-2-Pad3)") (class "Default")
      (node (ref "U8") (pin "3") (pinfunction "2_3") (pintype "bidirectional"))
    )
    (net (code "108") (name "unconnected-(U8-3-Pad4)") (class "Default")
      (node (ref "U8") (pin "4") (pinfunction "3_4") (pintype "bidirectional"))
    )
    (net (code "109") (name "unconnected-(U8-4-Pad5)") (class "Default")
      (node (ref "U8") (pin "5") (pinfunction "4_5") (pintype "bidirectional"))
    )
    (net (code "110") (name "unconnected-(U8-5-Pad6)") (class "Default")
      (node (ref "U8") (pin "6") (pinfunction "5_6") (pintype "bidirectional"))
    )
    (net (code "111") (name "unconnected-(U8-6-Pad7)") (class "Default")
      (node (ref "U8") (pin "7") (pinfunction "6_7") (pintype "bidirectional"))
    )
    (net (code "112") (name "unconnected-(U8-7-Pad9)") (class "Default")
      (node (ref "U8") (pin "9") (pinfunction "7_9") (pintype "bidirectional"))
    )
    (net (code "113") (name "unconnected-(U8-8-Pad10)") (class "Default")
      (node (ref "U8") (pin "10") (pinfunction "8_10") (pintype "bidirectional"))
    )
    (net (code "114") (name "unconnected-(U8-9-Pad11)") (class "Default")
      (node (ref "U8") (pin "11") (pinfunction "9_11") (pintype "bidirectional"))
    )
    (net (code "115") (name "unconnected-(U9-0-Pad1)") (class "Default")
      (node (ref "U9") (pin "1") (pinfunction "0_1") (pintype "bidirectional"))
    )
    (net (code "116") (name "unconnected-(U9-1-Pad2)") (class "Default")
      (node (ref "U9") (pin "2") (pinfunction "1_2") (pintype "bidirectional"))
    )
    (net (code "117") (name "unconnected-(U9-2-Pad3)") (class "Default")
      (node (ref "U9") (pin "3") (pinfunction "2_3") (pintype "bidirectional"))
    )
    (net (code "118") (name "unconnected-(U9-3-Pad4)") (class "Default")
      (node (ref "U9") (pin "4") (pinfunction "3_4") (pintype "bidirectional"))
    )
    (net (code "119") (name "unconnected-(U9-4-Pad5)") (class "Default")
      (node (ref "U9") (pin "5") (pinfunction "4_5") (pintype "bidirectional"))
    )
    (net (code "120") (name "unconnected-(U9-5-Pad6)") (class "Default")
      (node (ref "U9") (pin "6") (pinfunction "5_6") (pintype "bidirectional"))
    )
    (net (code "121") (name "unconnected-(U9-6-Pad7)") (class "Default")
      (node (ref "U9") (pin "7") (pinfunction "6_7") (pintype "bidirectional"))
    )
    (net (code "122") (name "unconnected-(U9-7-Pad9)") (class "Default")
      (node (ref "U9") (pin "9") (pinfunction "7_9") (pintype "bidirectional"))
    )
    (net (code "123") (name "unconnected-(U9-8-Pad10)") (class "Default")
      (node (ref "U9") (pin "10") (pinfunction "8_10") (pintype "bidirectional"))
    )
    (net (code "124") (name "unconnected-(U9-9-Pad11)") (class "Default")
      (node (ref "U9") (pin "11") (pinfunction "9_11") (pintype "bidirectional"))
    )
    (net (code "125") (name "unconnected-(U10-0-Pad1)") (class "Default")
      (node (ref "U10") (pin "1") (pinfunction "0_1") (pintype "bidirectional"))
    )
    (net (code "126") (name "unconnected-(U10-1-Pad2)") (class "Default")
      (node (ref "U10") (pin "2") (pinfunction "1_2") (pintype "bidirectional"))
    )
    (net (code "127") (name "unconnected-(U10-2-Pad3)") (class "Default")
      (node (ref "U10") (pin "3") (pinfunction "2_3") (pintype "bidirectional"))
    )
    (net (code "128") (name "unconnected-(U10-3-Pad4)") (class "Default")
      (node (ref "U10") (pin "4") (pinfunction "3_4") (pintype "bidirectional"))
    )
    (net (code "129") (name "unconnected-(U10-4-Pad5)") (class "Default")
      (node (ref "U10") (pin "5") (pinfunction "4_5") (pintype "bidirectional"))
    )
    (net (code "130") (name "unconnected-(U10-5-Pad6)") (class "Default")
      (node (ref "U10") (pin "6") (pinfunction "5_6") (pintype "bidirectional"))
    )
    (net (code "131") (name "unconnected-(U10-6-Pad7)") (class "Default")
      (node (ref "U10") (pin "7") (pinfunction "6_7") (pintype "bidirectional"))
    )
    (net (code "132") (name "unconnected-(U10-7-Pad9)") (class "Default")
      (node (ref "U10") (pin "9") (pinfunction "7_9") (pintype "bidirectional"))
    )
    (net (code "133") (name "unconnected-(U10-8-Pad10)") (class "Default")
      (node (ref "U10") (pin "10") (pinfunction "8_10") (pintype "bidirectional"))
    )
    (net (code "134") (name "unconnected-(U10-9-Pad11)") (class "Default")
      (node (ref "U10") (pin "11") (pinfunction "9_11") (pintype "bidirectional"))
    )
    (net (code "135") (name "unconnected-(U11-Q0-Pad15)") (class "Default")
      (node (ref "U11") (pin "15") (pinfunction "Q0_15") (pintype "bidirectional"))
    )
    (net (code "136") (name "unconnected-(U11-Q1-Pad1)") (class "Default")
      (node (ref "U11") (pin "1") (pinfunction "Q1_1") (pintype "bidirectional"))
    )
    (net (code "137") (name "unconnected-(U11-Q2-Pad2)") (class "Default")
      (node (ref "U11") (pin "2") (pinfunction "Q2_2") (pintype "bidirectional"))
    )
    (net (code "138") (name "unconnected-(U11-Q3-Pad3)") (class "Default")
      (node (ref "U11") (pin "3") (pinfunction "Q3_3") (pintype "bidirectional"))
    )
    (net (code "139") (name "unconnected-(U11-Q4-Pad4)") (class "Default")
      (node (ref "U11") (pin "4") (pinfunction "Q4_4") (pintype "bidirectional"))
    )
    (net (code "140") (name "unconnected-(U11-Q5-Pad5)") (class "Default")
      (node (ref "U11") (pin "5") (pinfunction "Q5_5") (pintype "bidirectional"))
    )
    (net (code "141") (name "unconnected-(U11-Q6-Pad6)") (class "Default")
      (node (ref "U11") (pin "6") (pinfunction "Q6_6") (pintype "bidirectional"))
    )
    (net (code "142") (name "unconnected-(U11-Q7-Pad7)") (class "Default")
      (node (ref "U11") (pin "7") (pinfunction "Q7_7") (pintype "bidirectional"))
    )
    (net (code "143") (name "unconnected-(U11-Q7S-Pad9)") (class "Default")
      (node (ref "U11") (pin "9") (pinfunction "Q7S_9") (pintype "bidirectional"))
    )
  )
)
